# 05-PWR.net
KiCad netlist of a schematic drawn in EAGLE
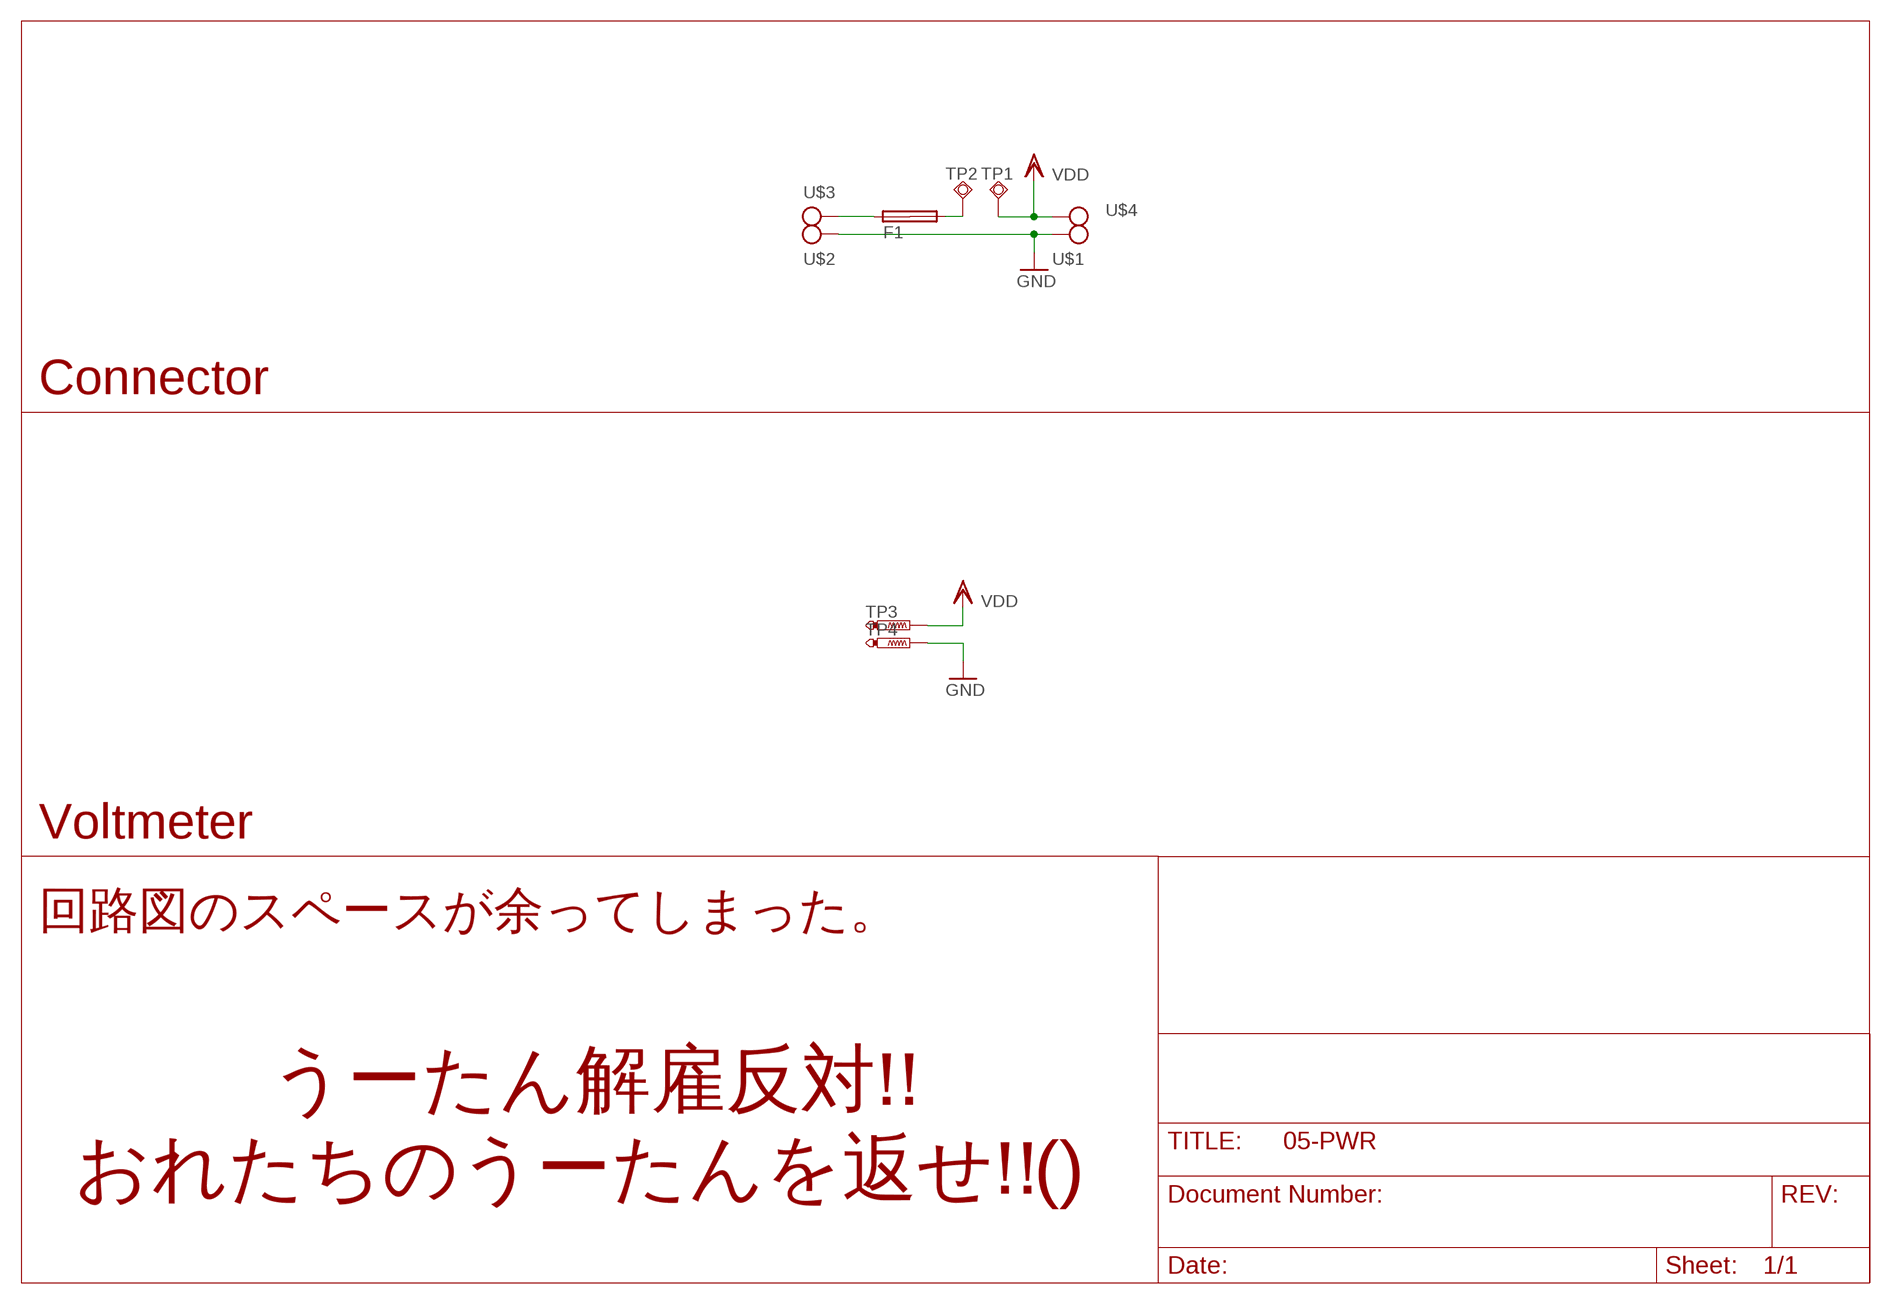
[diagram p0: schematic, sheet 1]

(export (version "E")
  (design (tool "Eeschema 10.0.6"))
  (components
    (comp (ref "F1")
      (value "SHK20L")
      (footprint "eagle-import:SHK20L")
      (libsource (lib "eagle-import") (part "SHK20L"))
    )
    (comp (ref "TP1")
      (value "TPSQPAD1-20")
      (footprint "eagle-import:P1-20")
      (libsource (lib "eagle-import") (part "TPSQPAD1-20"))
    )
    (comp (ref "TP2")
      (value "TPSQPAD1-20")
      (footprint "eagle-import:P1-20")
      (libsource (lib "eagle-import") (part "TPSQPAD1-20"))
    )
    (comp (ref "TP3")
      (value "PTR1TP15R")
      (footprint "eagle-import:TP15R")
      (libsource (lib "eagle-import") (part "PTR1TP15R"))
    )
    (comp (ref "TP4")
      (value "PTR1TP15SQ")
      (footprint "eagle-import:TP15SQ")
      (libsource (lib "eagle-import") (part "PTR1TP15SQ"))
    )
    (comp (ref "U$1")
      (value "PAD_VDD")
      (footprint "eagle-import:VDD")
      (libsource (lib "eagle-import") (part "PAD_VDD"))
    )
    (comp (ref "U$2")
      (value "PAD_VDD")
      (footprint "eagle-import:VDD")
      (libsource (lib "eagle-import") (part "PAD_VDD"))
    )
    (comp (ref "U$3")
      (value "PAD_VDD")
      (footprint "eagle-import:VDD")
      (libsource (lib "eagle-import") (part "PAD_VDD"))
    )
    (comp (ref "U$4")
      (value "PAD_VDD")
      (footprint "eagle-import:VDD")
      (libsource (lib "eagle-import") (part "PAD_VDD"))
    )
  )
  (nets
    (net (code "1") (name "GND") (class "Default")
      (node (ref "TP4") (pin "TP") (pinfunction "TP_TP") (pintype "input"))
      (node (ref "U$1") (pin "P$1") (pinfunction "TP_P$1") (pintype "input"))
      (node (ref "U$2") (pin "P$1") (pinfunction "TP_P$1") (pintype "input"))
    )
    (net (code "2") (name "Net-(F1-Pad2A)") (class "Default")
      (node (ref "F1") (pin "2A") (pinfunction "2A_2A") (pintype "passive"))
      (node (ref "TP2") (pin "TP") (pinfunction "TP_TP") (pintype "input"))
    )
    (net (code "3") (name "Net-(U$3-TP)") (class "Default")
      (node (ref "F1") (pin "1A") (pinfunction "1A_1A") (pintype "passive"))
      (node (ref "U$3") (pin "P$1") (pinfunction "TP_P$1") (pintype "input"))
    )
    (net (code "4") (name "VDD") (class "Default")
      (node (ref "TP1") (pin "TP") (pinfunction "TP_TP") (pintype "input"))
      (node (ref "TP3") (pin "TP") (pinfunction "TP_TP") (pintype "input"))
      (node (ref "U$4") (pin "P$1") (pinfunction "TP_P$1") (pintype "input"))
    )
    (net (code "5") (name "unconnected-(F1-Pad1B)") (class "Default")
      (node (ref "F1") (pin "1B") (pinfunction "1B_1B") (pintype "passive"))
    )
    (net (code "6") (name "unconnected-(F1-Pad2B)") (class "Default")
      (node (ref "F1") (pin "2B") (pinfunction "2B_2B") (pintype "passive"))
    )
  )
)
